# Lights.net
KiCad netlist of a schematic drawn in EAGLE
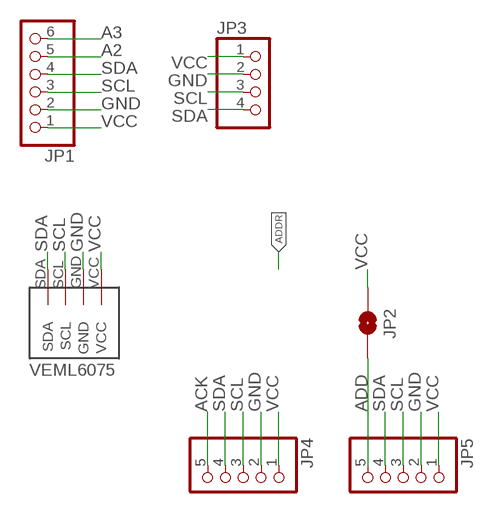
[diagram p0: schematic, sheet 1]

(export (version "E")
  (design (tool "Eeschema 10.0.6"))
  (components
    (comp (ref "JP1")
      (value "PINHD-1X6")
      (footprint "eagle-import:1X06")
      (libsource (lib "eagle-import") (part "PINHD-1X6"))
    )
    (comp (ref "JP2")
      (value "JUMPER-SMT_2_NO_SILK")
      (footprint "eagle-import:SMT-JUMPER_2_NO_SILK")
      (libsource (lib "eagle-import") (part "JUMPER-SMT_2_NO_SILK"))
    )
    (comp (ref "JP3")
      (value "PINHD-1X4")
      (footprint "eagle-import:1X04")
      (libsource (lib "eagle-import") (part "PINHD-1X4"))
    )
    (comp (ref "JP4")
      (value "PINHD-1X5")
      (footprint "eagle-import:1X05")
      (libsource (lib "eagle-import") (part "PINHD-1X5"))
    )
    (comp (ref "JP5")
      (value "PINHD-1X5")
      (footprint "eagle-import:1X05")
      (libsource (lib "eagle-import") (part "PINHD-1X5"))
    )
    (comp (ref "U$2")
      (value "VEML6075")
      (footprint "eagle-import:VEML6075")
      (libsource (lib "eagle-import") (part "VEML6075"))
    )
  )
  (nets
    (net (code "1") (name "/A2") (class "Default")
      (node (ref "JP1") (pin "5") (pinfunction "5_5") (pintype "passive"))
    )
    (net (code "2") (name "/A3") (class "Default")
      (node (ref "JP1") (pin "6") (pinfunction "6_6") (pintype "passive"))
    )
    (net (code "3") (name "/ACK") (class "Default")
      (node (ref "JP4") (pin "5") (pinfunction "5_5") (pintype "passive"))
    )
    (net (code "4") (name "/ADD") (class "Default")
      (node (ref "JP2") (pin "1") (pinfunction "1_1") (pintype "passive"))
      (node (ref "JP5") (pin "5") (pinfunction "5_5") (pintype "passive"))
    )
    (net (code "5") (name "/GND") (class "Default")
      (node (ref "JP1") (pin "2") (pinfunction "2_2") (pintype "passive"))
      (node (ref "JP3") (pin "2") (pinfunction "2_2") (pintype "passive"))
      (node (ref "JP4") (pin "2") (pinfunction "2_2") (pintype "passive"))
      (node (ref "JP5") (pin "2") (pinfunction "2_2") (pintype "passive"))
      (node (ref "U$2") (pin "GND") (pinfunction "GND_GND") (pintype "bidirectional"))
    )
    (net (code "6") (name "/SCL") (class "Default")
      (node (ref "JP1") (pin "3") (pinfunction "3_3") (pintype "passive"))
      (node (ref "JP3") (pin "3") (pinfunction "3_3") (pintype "passive"))
      (node (ref "JP4") (pin "3") (pinfunction "3_3") (pintype "passive"))
      (node (ref "JP5") (pin "3") (pinfunction "3_3") (pintype "passive"))
      (node (ref "U$2") (pin "SCL") (pinfunction "SCL_SCL") (pintype "bidirectional"))
    )
    (net (code "7") (name "/SDA") (class "Default")
      (node (ref "JP1") (pin "4") (pinfunction "4_4") (pintype "passive"))
      (node (ref "JP3") (pin "4") (pinfunction "4_4") (pintype "passive"))
      (node (ref "JP4") (pin "4") (pinfunction "4_4") (pintype "passive"))
      (node (ref "JP5") (pin "4") (pinfunction "4_4") (pintype "passive"))
      (node (ref "U$2") (pin "SDA") (pinfunction "SDA_SDA") (pintype "bidirectional"))
    )
    (net (code "8") (name "/VCC") (class "Default")
      (node (ref "JP1") (pin "1") (pinfunction "1_1") (pintype "passive"))
      (node (ref "JP2") (pin "2") (pinfunction "2_2") (pintype "passive"))
      (node (ref "JP3") (pin "1") (pinfunction "1_1") (pintype "passive"))
      (node (ref "JP4") (pin "1") (pinfunction "1_1") (pintype "passive"))
      (node (ref "JP5") (pin "1") (pinfunction "1_1") (pintype "passive"))
      (node (ref "U$2") (pin "VCC") (pinfunction "VCC_VCC") (pintype "bidirectional"))
    )
  )
)
